# Timer_CMD.net
KiCad netlist of a schematic drawn in EAGLE
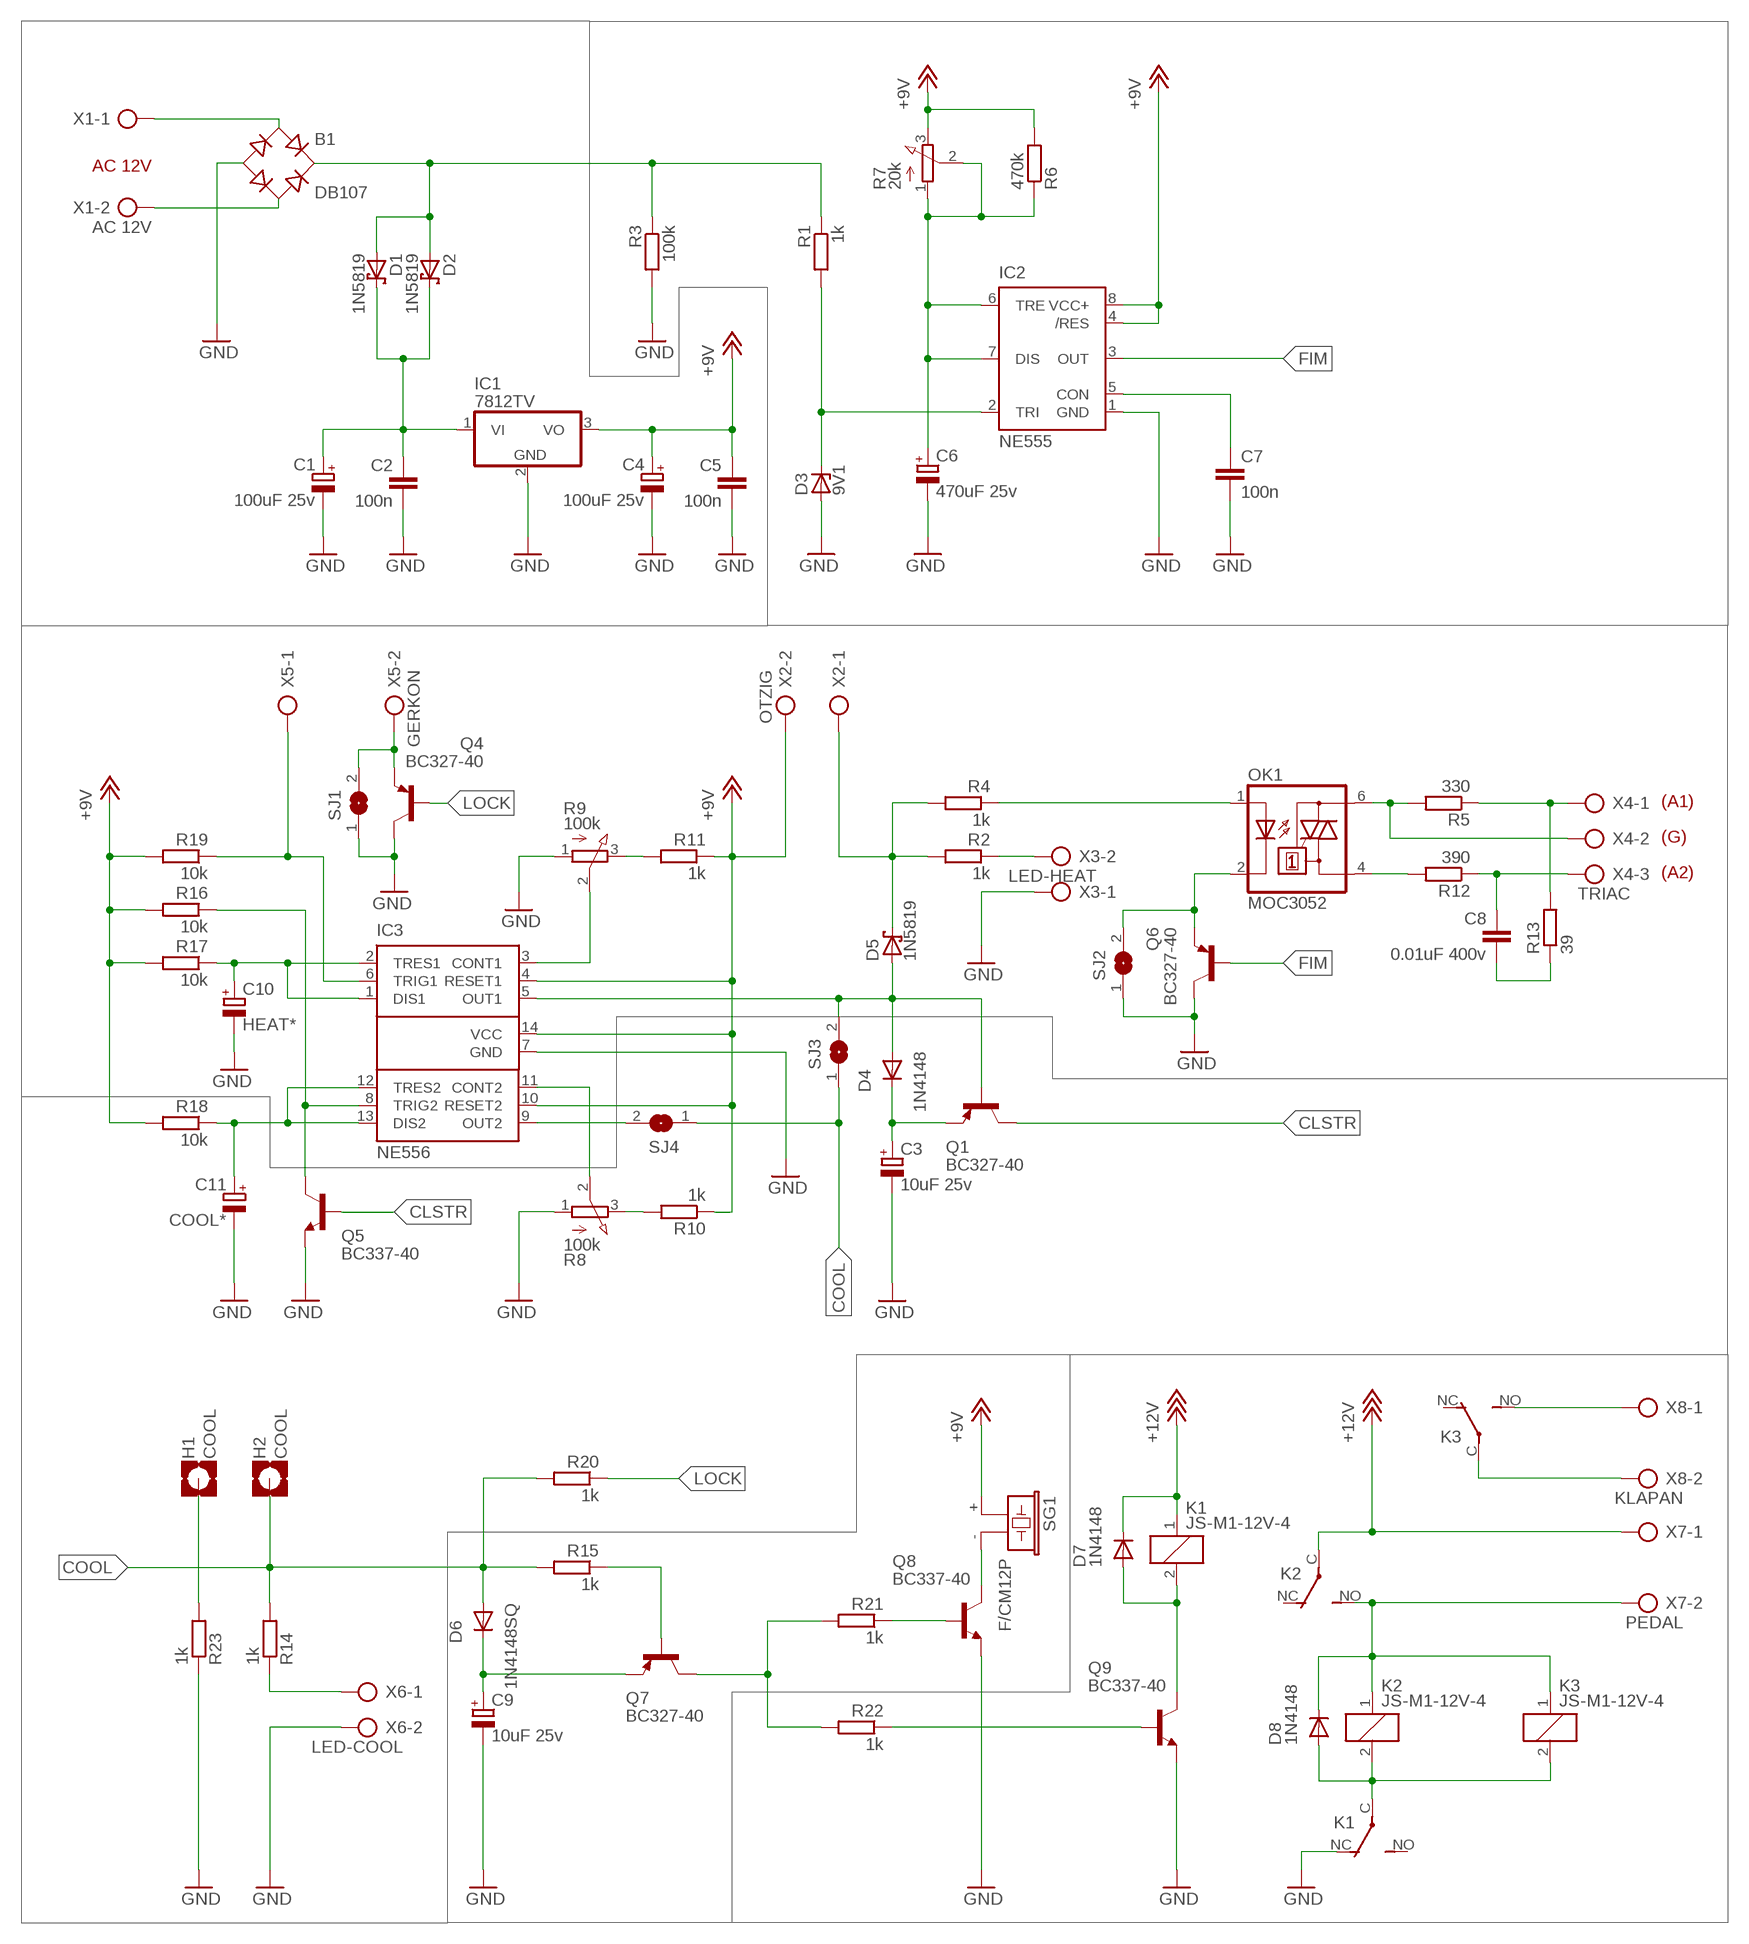
[diagram p0: schematic, sheet 1]

(export (version "E")
  (design (tool "Eeschema 10.0.6"))
  (components
    (comp (ref "B1")
      (value "DB107")
      (footprint "eagle-import:DB")
      (libsource (lib "eagle-import") (part "DB?GDB107"))
    )
    (comp (ref "C1")
      (value "100uF 25v")
      (footprint "eagle-import:E3,5-8")
      (libsource (lib "eagle-import") (part "CPOL-EUE3.5-8"))
    )
    (comp (ref "C2")
      (value "100n")
      (footprint "eagle-import:C025-030X050")
      (libsource (lib "eagle-import") (part "C-EU025-030X050"))
    )
    (comp (ref "C3")
      (value "10uF 25v")
      (footprint "eagle-import:E3,5-8")
      (libsource (lib "eagle-import") (part "CPOL-EUE3.5-8"))
    )
    (comp (ref "C4")
      (value "100uF 25v")
      (footprint "eagle-import:E3,5-8")
      (libsource (lib "eagle-import") (part "CPOL-EUE3.5-8"))
    )
    (comp (ref "C5")
      (value "100n")
      (footprint "eagle-import:C025-030X050")
      (libsource (lib "eagle-import") (part "C-EU025-030X050"))
    )
    (comp (ref "C6")
      (value "470uF 25v")
      (footprint "eagle-import:E3,5-8")
      (libsource (lib "eagle-import") (part "CPOL-EUE3.5-8"))
    )
    (comp (ref "C7")
      (value "100n")
      (footprint "eagle-import:C050-035X075")
      (libsource (lib "eagle-import") (part "C-EU050-035X075"))
    )
    (comp (ref "C8")
      (value "0.01uF 400v")
      (footprint "eagle-import:C075-063X106")
      (libsource (lib "eagle-import") (part "C-EU075-063X106"))
    )
    (comp (ref "C9")
      (value "10uF 25v")
      (footprint "eagle-import:E3,5-8")
      (libsource (lib "eagle-import") (part "CPOL-EUE3.5-8"))
    )
    (comp (ref "C10")
      (value "HEAT*")
      (footprint "eagle-import:E3,5-10")
      (libsource (lib "eagle-import") (part "CPOL-EUE3.5-10"))
    )
    (comp (ref "C11")
      (value "COOL*")
      (footprint "eagle-import:E3,5-10")
      (libsource (lib "eagle-import") (part "CPOL-EUE3.5-10"))
    )
    (comp (ref "D1")
      (value "1N5819")
      (footprint "eagle-import:DO41-7.6")
      (libsource (lib "eagle-import") (part "1N5819-T"))
    )
    (comp (ref "D2")
      (value "1N5819")
      (footprint "eagle-import:DO41-7.6")
      (libsource (lib "eagle-import") (part "1N5819-T"))
    )
    (comp (ref "D3")
      (value "9V1")
      (footprint "eagle-import:DO41Z10")
      (libsource (lib "eagle-import") (part "1N4728"))
    )
    (comp (ref "D4")
      (value "1N4148")
      (footprint "eagle-import:DO35-7SQ")
      (libsource (lib "eagle-import") (part "1N4148S"))
    )
    (comp (ref "D5")
      (value "1N5819")
      (footprint "eagle-import:DO41-7.6")
      (libsource (lib "eagle-import") (part "1N5819-T"))
    )
    (comp (ref "D6")
      (value "1N4148SQ")
      (footprint "eagle-import:DO35-10_SQ")
      (libsource (lib "eagle-import") (part "1N4148SQ"))
    )
    (comp (ref "D7")
      (value "1N4148")
      (footprint "eagle-import:DO35-7SQ")
      (libsource (lib "eagle-import") (part "1N4148S"))
    )
    (comp (ref "D8")
      (value "1N4148")
      (footprint "eagle-import:DO35-7SQ")
      (libsource (lib "eagle-import") (part "1N4148S"))
    )
    (comp (ref "H1")
      (value "COOL")
      (footprint "eagle-import:4MM-PAD-SQUARE")
      (libsource (lib "eagle-import") (part "MOUNT-PAD-SQUARE"))
    )
    (comp (ref "H2")
      (value "COOL")
      (footprint "eagle-import:4MM-PAD-SQUARE")
      (libsource (lib "eagle-import") (part "MOUNT-PAD-SQUARE"))
    )
    (comp (ref "IC1")
      (value "7812TV")
      (footprint "eagle-import:TO220V")
      (libsource (lib "eagle-import") (part "78TV12"))
    )
    (comp (ref "IC2")
      (value "NE555")
      (footprint "eagle-import:DIL-08")
      (fields (field (name "MF") "Arrow Electronics") (field (name "MPN") "NE555N"))
      (libsource (lib "eagle-import") (part "NE555"))
    )
    (comp (ref "IC3")
      (value "NE556")
      (footprint "eagle-import:DIL14")
      (libsource (lib "eagle-import") (part "NE556"))
    )
    (comp (ref "K1")
      (value "JS-M1-12V-4")
      (footprint "eagle-import:JS-M")
      (fields (field (name "MPN") "JSM1-12V-4"))
      (libsource (lib "eagle-import") (part "JS-M1-12V-4"))
    )
    (comp (ref "K2")
      (value "JS-M1-12V-4")
      (footprint "eagle-import:JS-M")
      (fields (field (name "MPN") "JSM1-12V-4"))
      (libsource (lib "eagle-import") (part "JS-M1-12V-4"))
    )
    (comp (ref "K3")
      (value "JS-M1-12V-4")
      (footprint "eagle-import:JS-M")
      (fields (field (name "MPN") "JSM1-12V-4"))
      (libsource (lib "eagle-import") (part "JS-M1-12V-4"))
    )
    (comp (ref "OK1")
      (value "MOC3052")
      (footprint "eagle-import:DIL06")
      (fields (field (name "MF") "FAIRCHILD SEMICONDUCTOR") (field (name "MPN") "MOC3042-M"))
      (libsource (lib "eagle-import") (part "MOC3042M"))
    )
    (comp (ref "Q1")
      (value "BC327-40")
      (footprint "eagle-import:TO92-EBC")
      (libsource (lib "eagle-import") (part "BC327-40"))
    )
    (comp (ref "Q4")
      (value "BC327-40")
      (footprint "eagle-import:TO92-EBC")
      (libsource (lib "eagle-import") (part "BC327-40"))
    )
    (comp (ref "Q5")
      (value "BC337-40")
      (footprint "eagle-import:TO92-EBC")
      (libsource (lib "eagle-import") (part "BC338-40"))
    )
    (comp (ref "Q6")
      (value "BC327-40")
      (footprint "eagle-import:TO92-EBC")
      (libsource (lib "eagle-import") (part "BC327-40"))
    )
    (comp (ref "Q7")
      (value "BC327-40")
      (footprint "eagle-import:TO92-EBC")
      (libsource (lib "eagle-import") (part "BC327-40"))
    )
    (comp (ref "Q8")
      (value "BC337-40")
      (footprint "eagle-import:TO92-EBC")
      (libsource (lib "eagle-import") (part "BC338-40"))
    )
    (comp (ref "Q9")
      (value "BC337-40")
      (footprint "eagle-import:TO92-EBC")
      (libsource (lib "eagle-import") (part "BC338-40"))
    )
    (comp (ref "R1")
      (value "1k")
      (footprint "eagle-import:0207_10")
      (libsource (lib "eagle-import") (part "R-EU_0207/10"))
    )
    (comp (ref "R2")
      (value "1k")
      (footprint "eagle-import:0207_10")
      (libsource (lib "eagle-import") (part "R-EU_0207/10"))
    )
    (comp (ref "R3")
      (value "100k")
      (footprint "eagle-import:0207_10")
      (libsource (lib "eagle-import") (part "R-EU_0207/10"))
    )
    (comp (ref "R4")
      (value "1k")
      (footprint "eagle-import:0207_10")
      (libsource (lib "eagle-import") (part "R-EU_0207/10"))
    )
    (comp (ref "R5")
      (value "330")
      (footprint "eagle-import:0207_10")
      (libsource (lib "eagle-import") (part "R-EU_0207/10"))
    )
    (comp (ref "R6")
      (value "470k")
      (footprint "eagle-import:0207_10")
      (libsource (lib "eagle-import") (part "R-EU_0207/10"))
    )
    (comp (ref "R7")
      (value "20k")
      (footprint "eagle-import:3RP_1610N")
      (libsource (lib "eagle-import") (part "3RP/1610N"))
    )
    (comp (ref "R8")
      (value "100k")
      (footprint "eagle-import:3RP_1610N")
      (libsource (lib "eagle-import") (part "3RP/1610N"))
    )
    (comp (ref "R9")
      (value "100k")
      (footprint "eagle-import:3RP_1610N")
      (libsource (lib "eagle-import") (part "3RP/1610N"))
    )
    (comp (ref "R10")
      (value "1k")
      (footprint "eagle-import:0207_10")
      (libsource (lib "eagle-import") (part "R-EU_0207/10"))
    )
    (comp (ref "R11")
      (value "1k")
      (footprint "eagle-import:0207_10")
      (libsource (lib "eagle-import") (part "R-EU_0207/10"))
    )
    (comp (ref "R12")
      (value "390")
      (footprint "eagle-import:0207_10")
      (libsource (lib "eagle-import") (part "R-EU_0207/10"))
    )
    (comp (ref "R13")
      (value "39")
      (footprint "eagle-import:0411_12")
      (libsource (lib "eagle-import") (part "R-EU_0411/12"))
    )
    (comp (ref "R14")
      (value "1k")
      (footprint "eagle-import:0207_10")
      (libsource (lib "eagle-import") (part "R-EU_0207/10"))
    )
    (comp (ref "R15")
      (value "1k")
      (footprint "eagle-import:0207_10")
      (libsource (lib "eagle-import") (part "R-EU_0207/10"))
    )
    (comp (ref "R16")
      (value "10k")
      (footprint "eagle-import:0207_10")
      (libsource (lib "eagle-import") (part "R-EU_0207/10"))
    )
    (comp (ref "R17")
      (value "10k")
      (footprint "eagle-import:0207_10")
      (libsource (lib "eagle-import") (part "R-EU_0207/10"))
    )
    (comp (ref "R18")
      (value "10k")
      (footprint "eagle-import:0207_10")
      (libsource (lib "eagle-import") (part "R-EU_0207/10"))
    )
    (comp (ref "R19")
      (value "10k")
      (footprint "eagle-import:0207_10")
      (libsource (lib "eagle-import") (part "R-EU_0207/10"))
    )
    (comp (ref "R20")
      (value "1k")
      (footprint "eagle-import:0207_10")
      (libsource (lib "eagle-import") (part "R-EU_0207/10"))
    )
    (comp (ref "R21")
      (value "1k")
      (footprint "eagle-import:0207_10")
      (libsource (lib "eagle-import") (part "R-EU_0207/10"))
    )
    (comp (ref "R22")
      (value "1k")
      (footprint "eagle-import:0207_10")
      (libsource (lib "eagle-import") (part "R-EU_0207/10"))
    )
    (comp (ref "R23")
      (value "1k")
      (footprint "eagle-import:0207_10")
      (libsource (lib "eagle-import") (part "R-EU_0207/10"))
    )
    (comp (ref "SG1")
      (value "F/CM12P")
      (footprint "eagle-import:F_CM12P")
      (libsource (lib "eagle-import") (part "F/CM12P"))
    )
    (comp (ref "SJ1") (value "SJ") (footprint "eagle-import:SJ") (libsource (lib "eagle-import") (part "SJ")))
    (comp (ref "SJ2") (value "SJ") (footprint "eagle-import:SJ") (libsource (lib "eagle-import") (part "SJ")))
    (comp (ref "SJ3") (value "SJ") (footprint "eagle-import:SJ") (libsource (lib "eagle-import") (part "SJ")))
    (comp (ref "SJ4") (value "SJ") (footprint "eagle-import:SJ") (libsource (lib "eagle-import") (part "SJ")))
    (comp (ref "X1")
      (value "AC 12V")
      (footprint "eagle-import:AK500_2")
      (libsource (lib "eagle-import") (part "AK500/2"))
    )
    (comp (ref "X2")
      (value "OTZIG")
      (footprint "eagle-import:AK500_2")
      (libsource (lib "eagle-import") (part "AK500/2"))
    )
    (comp (ref "X3")
      (value "LED-HEAT")
      (footprint "eagle-import:AK500_2")
      (libsource (lib "eagle-import") (part "AK500/2"))
    )
    (comp (ref "X4")
      (value "TRIAC")
      (footprint "eagle-import:AK500_3")
      (libsource (lib "eagle-import") (part "AK500/3"))
    )
    (comp (ref "X5")
      (value "GERKON")
      (footprint "eagle-import:AK500_2")
      (libsource (lib "eagle-import") (part "AK500/2"))
    )
    (comp (ref "X6")
      (value "LED-COOL")
      (footprint "eagle-import:AK500_2")
      (libsource (lib "eagle-import") (part "AK500/2"))
    )
    (comp (ref "X7")
      (value "PEDAL")
      (footprint "eagle-import:AK500_2")
      (libsource (lib "eagle-import") (part "AK500/2"))
    )
    (comp (ref "X8")
      (value "KLAPAN")
      (footprint "eagle-import:AK500_2")
      (libsource (lib "eagle-import") (part "AK500/2"))
    )
  )
  (nets
    (net (code "1") (name "+9V") (class "Default")
      (node (ref "C4") (pin "+") (pinfunction "+_+") (pintype "passive"))
      (node (ref "C5") (pin "1") (pinfunction "1_1") (pintype "passive"))
      (node (ref "IC1") (pin "3") (pinfunction "VO_3") (pintype "passive"))
      (node (ref "IC2") (pin "4") (pinfunction "/RES_4") (pintype "input"))
      (node (ref "IC2") (pin "8") (pinfunction "VCC+_8") (pintype "power_in"))
      (node (ref "IC3") (pin "10") (pinfunction "RESET2_10") (pintype "input"))
      (node (ref "IC3") (pin "14") (pinfunction "VCC_14") (pintype "power_in"))
      (node (ref "IC3") (pin "4") (pinfunction "RESET1_4") (pintype "input"))
      (node (ref "R10") (pin "1") (pinfunction "1_1") (pintype "passive"))
      (node (ref "R11") (pin "1") (pinfunction "1_1") (pintype "passive"))
      (node (ref "R16") (pin "2") (pinfunction "2_2") (pintype "passive"))
      (node (ref "R17") (pin "2") (pinfunction "2_2") (pintype "passive"))
      (node (ref "R18") (pin "2") (pinfunction "2_2") (pintype "passive"))
      (node (ref "R19") (pin "2") (pinfunction "2_2") (pintype "passive"))
      (node (ref "R6") (pin "2") (pinfunction "2_2") (pintype "passive"))
      (node (ref "R7") (pin "3") (pinfunction "E_3") (pintype "passive"))
      (node (ref "SG1") (pin "+") (pinfunction "1_+") (pintype "passive"))
      (node (ref "X2") (pin "2") (pinfunction "KL_2") (pintype "passive"))
    )
    (net (code "2") (name "+12V") (class "Default")
      (node (ref "D7") (pin "C") (pinfunction "C_C") (pintype "passive"))
      (node (ref "K1") (pin "1") (pinfunction "1_1") (pintype "passive"))
      (node (ref "K2") (pin "C") (pinfunction "P_C") (pintype "passive"))
      (node (ref "X7") (pin "1") (pinfunction "KL_1") (pintype "passive"))
    )
    (net (code "3") (name "CLSTR") (class "Default")
      (node (ref "Q1") (pin "C") (pinfunction "C_C") (pintype "passive"))
      (node (ref "Q5") (pin "B") (pinfunction "B_B") (pintype "passive"))
    )
    (net (code "4") (name "COOL") (class "Default")
      (node (ref "D6") (pin "A") (pinfunction "A_A") (pintype "passive"))
      (node (ref "H2") (pin "B2,8") (pinfunction "MOUNT_B2,8") (pintype "passive"))
      (node (ref "R14") (pin "2") (pinfunction "2_2") (pintype "passive"))
      (node (ref "R15") (pin "2") (pinfunction "2_2") (pintype "passive"))
      (node (ref "R20") (pin "2") (pinfunction "2_2") (pintype "passive"))
      (node (ref "SJ3") (pin "1") (pinfunction "1_1") (pintype "passive"))
      (node (ref "SJ4") (pin "1") (pinfunction "1_1") (pintype "passive"))
    )
    (net (code "5") (name "FIM") (class "Default")
      (node (ref "IC2") (pin "3") (pinfunction "OUT_3") (pintype "output"))
      (node (ref "Q6") (pin "B") (pinfunction "B_B") (pintype "passive"))
    )
    (net (code "6") (name "GND") (class "Default")
      (node (ref "B1") (pin "-") (pinfunction "-_-") (pintype "passive"))
      (node (ref "C1") (pin "-") (pinfunction "-_-") (pintype "passive"))
      (node (ref "C10") (pin "-") (pinfunction "-_-") (pintype "passive"))
      (node (ref "C11") (pin "-") (pinfunction "-_-") (pintype "passive"))
      (node (ref "C2") (pin "2") (pinfunction "2_2") (pintype "passive"))
      (node (ref "C3") (pin "-") (pinfunction "-_-") (pintype "passive"))
      (node (ref "C4") (pin "-") (pinfunction "-_-") (pintype "passive"))
      (node (ref "C5") (pin "2") (pinfunction "2_2") (pintype "passive"))
      (node (ref "C6") (pin "-") (pinfunction "-_-") (pintype "passive"))
      (node (ref "C7") (pin "2") (pinfunction "2_2") (pintype "passive"))
      (node (ref "C9") (pin "-") (pinfunction "-_-") (pintype "passive"))
      (node (ref "D3") (pin "A") (pinfunction "A_A") (pintype "passive"))
      (node (ref "IC1") (pin "2") (pinfunction "GND_2") (pintype "passive"))
      (node (ref "IC2") (pin "1") (pinfunction "GND_1") (pintype "power_in"))
      (node (ref "IC3") (pin "7") (pinfunction "GND_7") (pintype "power_in"))
      (node (ref "K1") (pin "NC") (pinfunction "O_NC") (pintype "passive"))
      (node (ref "Q4") (pin "C") (pinfunction "C_C") (pintype "passive"))
      (node (ref "Q5") (pin "E") (pinfunction "E_E") (pintype "passive"))
      (node (ref "Q6") (pin "C") (pinfunction "C_C") (pintype "passive"))
      (node (ref "Q8") (pin "E") (pinfunction "E_E") (pintype "passive"))
      (node (ref "Q9") (pin "E") (pinfunction "E_E") (pintype "passive"))
      (node (ref "R23") (pin "1") (pinfunction "1_1") (pintype "passive"))
      (node (ref "R3") (pin "2") (pinfunction "2_2") (pintype "passive"))
      (node (ref "R8") (pin "1") (pinfunction "A_1") (pintype "passive"))
      (node (ref "R9") (pin "1") (pinfunction "A_1") (pintype "passive"))
      (node (ref "SJ1") (pin "1") (pinfunction "1_1") (pintype "passive"))
      (node (ref "SJ2") (pin "1") (pinfunction "1_1") (pintype "passive"))
      (node (ref "X3") (pin "1") (pinfunction "KL_1") (pintype "passive"))
      (node (ref "X6") (pin "2") (pinfunction "KL_2") (pintype "passive"))
    )
    (net (code "7") (name "LOCK") (class "Default")
      (node (ref "Q4") (pin "B") (pinfunction "B_B") (pintype "passive"))
      (node (ref "R20") (pin "1") (pinfunction "1_1") (pintype "passive"))
    )
    (net (code "8") (name "Net-(B1-Pad+)") (class "Default")
      (node (ref "B1") (pin "+") (pinfunction "+_+") (pintype "passive"))
      (node (ref "D1") (pin "A") (pinfunction "A_A") (pintype "passive"))
      (node (ref "D2") (pin "A") (pinfunction "A_A") (pintype "passive"))
      (node (ref "R1") (pin "1") (pinfunction "1_1") (pintype "passive"))
      (node (ref "R3") (pin "1") (pinfunction "1_1") (pintype "passive"))
    )
    (net (code "9") (name "Net-(C3-Pad+)") (class "Default")
      (node (ref "C3") (pin "+") (pinfunction "+_+") (pintype "passive"))
      (node (ref "D4") (pin "C") (pinfunction "C_C") (pintype "passive"))
      (node (ref "Q1") (pin "E") (pinfunction "E_E") (pintype "passive"))
    )
    (net (code "10") (name "Net-(C8-Pad2)") (class "Default")
      (node (ref "C8") (pin "2") (pinfunction "2_2") (pintype "passive"))
      (node (ref "R13") (pin "1") (pinfunction "1_1") (pintype "passive"))
    )
    (net (code "11") (name "Net-(C9-Pad+)") (class "Default")
      (node (ref "C9") (pin "+") (pinfunction "+_+") (pintype "passive"))
      (node (ref "D6") (pin "C") (pinfunction "C_C") (pintype "passive"))
      (node (ref "Q7") (pin "E") (pinfunction "E_E") (pintype "passive"))
    )
    (net (code "12") (name "Net-(D7-PadA)") (class "Default")
      (node (ref "D7") (pin "A") (pinfunction "A_A") (pintype "passive"))
      (node (ref "K1") (pin "2") (pinfunction "2_2") (pintype "passive"))
      (node (ref "Q9") (pin "C") (pinfunction "C_C") (pintype "passive"))
    )
    (net (code "13") (name "Net-(H1-MOUNT)") (class "Default")
      (node (ref "H1") (pin "B2,8") (pinfunction "MOUNT_B2,8") (pintype "passive"))
      (node (ref "R23") (pin "2") (pinfunction "2_2") (pintype "passive"))
    )
    (net (code "14") (name "Net-(IC1-VI)") (class "Default")
      (node (ref "C1") (pin "+") (pinfunction "+_+") (pintype "passive"))
      (node (ref "C2") (pin "1") (pinfunction "1_1") (pintype "passive"))
      (node (ref "D1") (pin "C") (pinfunction "C_C") (pintype "passive"))
      (node (ref "D2") (pin "C") (pinfunction "C_C") (pintype "passive"))
      (node (ref "IC1") (pin "1") (pinfunction "VI_1") (pintype "input"))
    )
    (net (code "15") (name "Net-(IC2-CON)") (class "Default")
      (node (ref "C7") (pin "1") (pinfunction "1_1") (pintype "passive"))
      (node (ref "IC2") (pin "5") (pinfunction "CON_5") (pintype "input"))
    )
    (net (code "16") (name "Net-(IC2-DIS)") (class "Default")
      (node (ref "C6") (pin "+") (pinfunction "+_+") (pintype "passive"))
      (node (ref "IC2") (pin "6") (pinfunction "TRE_6") (pintype "input"))
      (node (ref "IC2") (pin "7") (pinfunction "DIS_7") (pintype "input"))
      (node (ref "R6") (pin "1") (pinfunction "1_1") (pintype "passive"))
      (node (ref "R7") (pin "1") (pinfunction "A_1") (pintype "passive"))
      (node (ref "R7") (pin "2") (pinfunction "S_2") (pintype "passive"))
    )
    (net (code "17") (name "Net-(IC2-TRI)") (class "Default")
      (node (ref "D3") (pin "C") (pinfunction "C_C") (pintype "passive"))
      (node (ref "IC2") (pin "2") (pinfunction "TRI_2") (pintype "input"))
      (node (ref "R1") (pin "2") (pinfunction "2_2") (pintype "passive"))
    )
    (net (code "18") (name "Net-(IC3-CONT1)") (class "Default")
      (node (ref "IC3") (pin "3") (pinfunction "CONT1_3") (pintype "input"))
      (node (ref "R9") (pin "2") (pinfunction "S_2") (pintype "passive"))
    )
    (net (code "19") (name "Net-(IC3-CONT2)") (class "Default")
      (node (ref "IC3") (pin "11") (pinfunction "CONT2_11") (pintype "input"))
      (node (ref "R8") (pin "2") (pinfunction "S_2") (pintype "passive"))
    )
    (net (code "20") (name "Net-(IC3-DIS1)") (class "Default")
      (node (ref "C10") (pin "+") (pinfunction "+_+") (pintype "passive"))
      (node (ref "IC3") (pin "1") (pinfunction "DIS1_1") (pintype "input"))
      (node (ref "IC3") (pin "2") (pinfunction "TRES1_2") (pintype "input"))
      (node (ref "R17") (pin "1") (pinfunction "1_1") (pintype "passive"))
    )
    (net (code "21") (name "Net-(IC3-DIS2)") (class "Default")
      (node (ref "C11") (pin "+") (pinfunction "+_+") (pintype "passive"))
      (node (ref "IC3") (pin "12") (pinfunction "TRES2_12") (pintype "input"))
      (node (ref "IC3") (pin "13") (pinfunction "DIS2_13") (pintype "input"))
      (node (ref "R18") (pin "1") (pinfunction "1_1") (pintype "passive"))
    )
    (net (code "22") (name "Net-(IC3-OUT1)") (class "Default")
      (node (ref "D4") (pin "A") (pinfunction "A_A") (pintype "passive"))
      (node (ref "D5") (pin "A") (pinfunction "A_A") (pintype "passive"))
      (node (ref "IC3") (pin "5") (pinfunction "OUT1_5") (pintype "output"))
      (node (ref "Q1") (pin "B") (pinfunction "B_B") (pintype "passive"))
      (node (ref "SJ3") (pin "2") (pinfunction "2_2") (pintype "passive"))
    )
    (net (code "23") (name "Net-(IC3-OUT2)") (class "Default")
      (node (ref "IC3") (pin "9") (pinfunction "OUT2_9") (pintype "output"))
      (node (ref "SJ4") (pin "2") (pinfunction "2_2") (pintype "passive"))
    )
    (net (code "24") (name "Net-(IC3-TRIG1)") (class "Default")
      (node (ref "IC3") (pin "6") (pinfunction "TRIG1_6") (pintype "input"))
      (node (ref "R19") (pin "1") (pinfunction "1_1") (pintype "passive"))
      (node (ref "X5") (pin "1") (pinfunction "KL_1") (pintype "passive"))
    )
    (net (code "25") (name "Net-(IC3-TRIG2)") (class "Default")
      (node (ref "IC3") (pin "8") (pinfunction "TRIG2_8") (pintype "input"))
      (node (ref "Q5") (pin "C") (pinfunction "C_C") (pintype "passive"))
      (node (ref "R16") (pin "1") (pinfunction "1_1") (pintype "passive"))
    )
    (net (code "26") (name "Net-(K1B-P)") (class "Default")
      (node (ref "D8") (pin "A") (pinfunction "A_A") (pintype "passive"))
      (node (ref "K1") (pin "C") (pinfunction "P_C") (pintype "passive"))
      (node (ref "K2") (pin "2") (pinfunction "2_2") (pintype "passive"))
      (node (ref "K3") (pin "2") (pinfunction "2_2") (pintype "passive"))
    )
    (net (code "27") (name "Net-(K2B-S)") (class "Default")
      (node (ref "D8") (pin "C") (pinfunction "C_C") (pintype "passive"))
      (node (ref "K2") (pin "1") (pinfunction "1_1") (pintype "passive"))
      (node (ref "K2") (pin "NO") (pinfunction "S_NO") (pintype "passive"))
      (node (ref "K3") (pin "1") (pinfunction "1_1") (pintype "passive"))
      (node (ref "X7") (pin "2") (pinfunction "KL_2") (pintype "passive"))
    )
    (net (code "28") (name "Net-(K3B-P)") (class "Default")
      (node (ref "K3") (pin "C") (pinfunction "P_C") (pintype "passive"))
      (node (ref "X8") (pin "2") (pinfunction "KL_2") (pintype "passive"))
    )
    (net (code "29") (name "Net-(K3B-S)") (class "Default")
      (node (ref "K3") (pin "NO") (pinfunction "S_NO") (pintype "passive"))
      (node (ref "X8") (pin "1") (pinfunction "KL_1") (pintype "passive"))
    )
    (net (code "30") (name "Net-(OK1-A)") (class "Default")
      (node (ref "OK1") (pin "1") (pinfunction "A_1") (pintype "passive"))
      (node (ref "R4") (pin "1") (pinfunction "1_1") (pintype "passive"))
    )
    (net (code "31") (name "Net-(OK1-A1)") (class "Default")
      (node (ref "OK1") (pin "4") (pinfunction "A1_4") (pintype "passive"))
      (node (ref "R12") (pin "2") (pinfunction "2_2") (pintype "passive"))
    )
    (net (code "32") (name "Net-(OK1-A2)") (class "Default")
      (node (ref "OK1") (pin "6") (pinfunction "A2_6") (pintype "passive"))
      (node (ref "R5") (pin "2") (pinfunction "2_2") (pintype "passive"))
      (node (ref "X4") (pin "2") (pinfunction "KL_2") (pintype "passive"))
    )
    (net (code "33") (name "Net-(OK1-C)") (class "Default")
      (node (ref "OK1") (pin "2") (pinfunction "C_2") (pintype "passive"))
      (node (ref "Q6") (pin "E") (pinfunction "E_E") (pintype "passive"))
      (node (ref "SJ2") (pin "2") (pinfunction "2_2") (pintype "passive"))
    )
    (net (code "34") (name "Net-(Q7-PadB)") (class "Default")
      (node (ref "Q7") (pin "B") (pinfunction "B_B") (pintype "passive"))
      (node (ref "R15") (pin "1") (pinfunction "1_1") (pintype "passive"))
    )
    (net (code "35") (name "Net-(Q7-PadC)") (class "Default")
      (node (ref "Q7") (pin "C") (pinfunction "C_C") (pintype "passive"))
      (node (ref "R21") (pin "2") (pinfunction "2_2") (pintype "passive"))
      (node (ref "R22") (pin "2") (pinfunction "2_2") (pintype "passive"))
    )
    (net (code "36") (name "Net-(Q8-PadB)") (class "Default")
      (node (ref "Q8") (pin "B") (pinfunction "B_B") (pintype "passive"))
      (node (ref "R21") (pin "1") (pinfunction "1_1") (pintype "passive"))
    )
    (net (code "37") (name "Net-(Q9-PadB)") (class "Default")
      (node (ref "Q9") (pin "B") (pinfunction "B_B") (pintype "passive"))
      (node (ref "R22") (pin "1") (pinfunction "1_1") (pintype "passive"))
    )
    (net (code "38") (name "Net-(R8-E)") (class "Default")
      (node (ref "R10") (pin "2") (pinfunction "2_2") (pintype "passive"))
      (node (ref "R8") (pin "3") (pinfunction "E_3") (pintype "passive"))
    )
    (net (code "39") (name "Net-(R9-E)") (class "Default")
      (node (ref "R11") (pin "2") (pinfunction "2_2") (pintype "passive"))
      (node (ref "R9") (pin "3") (pinfunction "E_3") (pintype "passive"))
    )
    (net (code "40") (name "Net-(SG1-2)") (class "Default")
      (node (ref "Q8") (pin "C") (pinfunction "C_C") (pintype "passive"))
      (node (ref "SG1") (pin "-") (pinfunction "2_-") (pintype "passive"))
    )
    (net (code "41") (name "Net-(X1A-KL)") (class "Default")
      (node (ref "B1") (pin "AC1") (pinfunction "AC1_AC1") (pintype "passive"))
      (node (ref "X1") (pin "1") (pinfunction "KL_1") (pintype "passive"))
    )
    (net (code "42") (name "Net-(X1B-KL)") (class "Default")
      (node (ref "B1") (pin "AC2") (pinfunction "AC2_AC2") (pintype "passive"))
      (node (ref "X1") (pin "2") (pinfunction "KL_2") (pintype "passive"))
    )
    (net (code "43") (name "Net-(X2A-KL)") (class "Default")
      (node (ref "D5") (pin "C") (pinfunction "C_C") (pintype "passive"))
      (node (ref "R2") (pin "2") (pinfunction "2_2") (pintype "passive"))
      (node (ref "R4") (pin "2") (pinfunction "2_2") (pintype "passive"))
      (node (ref "X2") (pin "1") (pinfunction "KL_1") (pintype "passive"))
    )
    (net (code "44") (name "Net-(X3B-KL)") (class "Default")
      (node (ref "R2") (pin "1") (pinfunction "1_1") (pintype "passive"))
      (node (ref "X3") (pin "2") (pinfunction "KL_2") (pintype "passive"))
    )
    (net (code "45") (name "Net-(X4A-KL)") (class "Default")
      (node (ref "R13") (pin "2") (pinfunction "2_2") (pintype "passive"))
      (node (ref "R5") (pin "1") (pinfunction "1_1") (pintype "passive"))
      (node (ref "X4") (pin "1") (pinfunction "KL_1") (pintype "passive"))
    )
    (net (code "46") (name "Net-(X4C-KL)") (class "Default")
      (node (ref "C8") (pin "1") (pinfunction "1_1") (pintype "passive"))
      (node (ref "R12") (pin "1") (pinfunction "1_1") (pintype "passive"))
      (node (ref "X4") (pin "3") (pinfunction "KL_3") (pintype "passive"))
    )
    (net (code "47") (name "Net-(X5B-KL)") (class "Default")
      (node (ref "Q4") (pin "E") (pinfunction "E_E") (pintype "passive"))
      (node (ref "SJ1") (pin "2") (pinfunction "2_2") (pintype "passive"))
      (node (ref "X5") (pin "2") (pinfunction "KL_2") (pintype "passive"))
    )
    (net (code "48") (name "Net-(X6A-KL)") (class "Default")
      (node (ref "R14") (pin "1") (pinfunction "1_1") (pintype "passive"))
      (node (ref "X6") (pin "1") (pinfunction "KL_1") (pintype "passive"))
    )
    (net (code "49") (name "unconnected-(K1B-S-PadNO)") (class "Default")
      (node (ref "K1") (pin "NO") (pinfunction "S_NO") (pintype "passive"))
    )
    (net (code "50") (name "unconnected-(K2B-O-PadNC)") (class "Default")
      (node (ref "K2") (pin "NC") (pinfunction "O_NC") (pintype "passive"))
    )
    (net (code "51") (name "unconnected-(K3B-O-PadNC)") (class "Default")
      (node (ref "K3") (pin "NC") (pinfunction "O_NC") (pintype "passive"))
    )
  )
)
